# STM89C52.net
KiCad netlist of a schematic drawn in Altium Designer
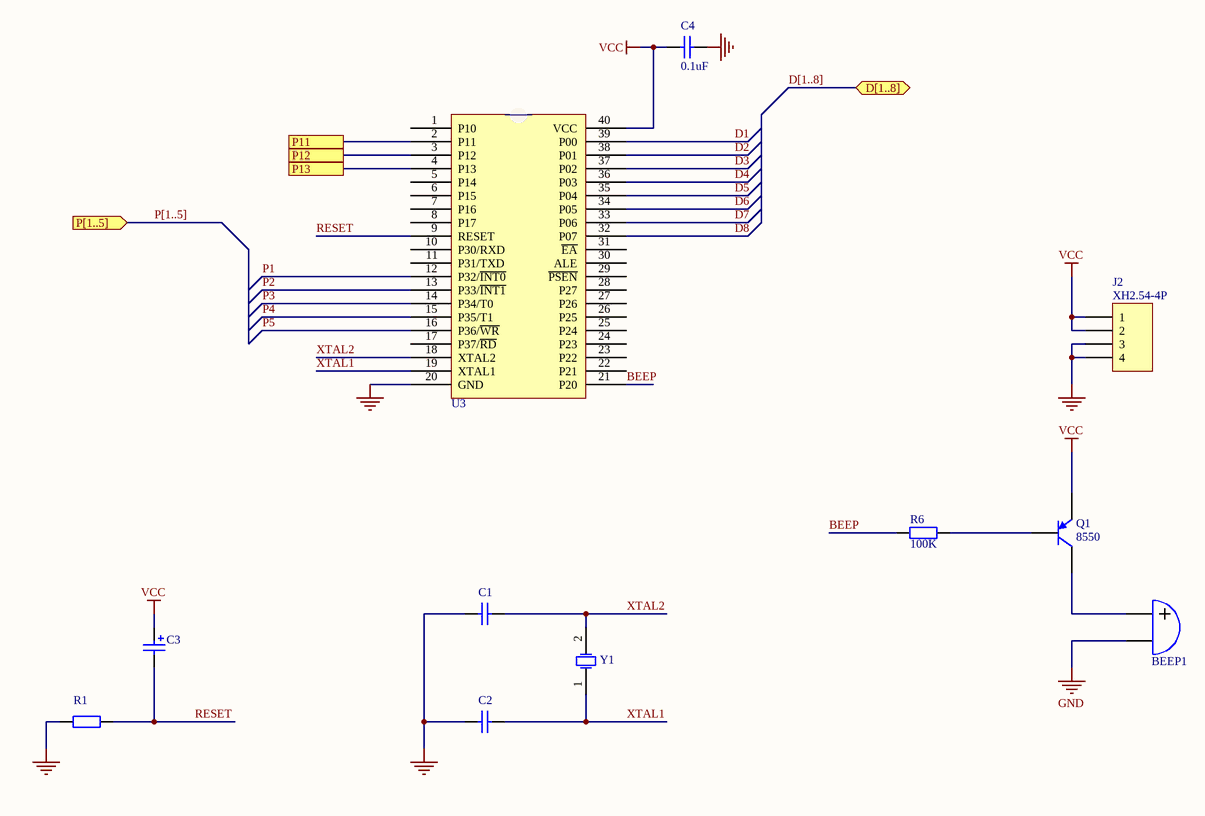
[diagram p0: STM89C52.SchDoc]

(export (version "E")
  (design (tool "Eeschema 10.0.6"))
  (components
    (comp (ref "BEEP1") (value "BEEP") (footprint "BEEP") (libsource (lib "TEST2024") (part "BEEP")))
    (comp (ref "C1")
      (value "Cap")
      (footprint "RAD-0.2")
      (description "Capacitor")
      (fields (field (name "PUBLISHER") "Altium Limited"))
      (libsource (lib "TEST2024") (part "Cap"))
    )
    (comp (ref "C2")
      (value "Cap")
      (footprint "RAD-0.2")
      (description "Capacitor")
      (fields (field (name "PUBLISHER") "Altium Limited"))
      (libsource (lib "TEST2024") (part "Cap"))
    )
    (comp (ref "C3")
      (value "Cap Pol1")
      (footprint "RB7.6-15")
      (description "Polarized Capacitor (Radial)")
      (fields (field (name "PUBLISHER") "Altium Limited"))
      (libsource (lib "TEST2024") (part "Cap Pol1"))
    )
    (comp (ref "C4")
      (value "0.1uF")
      (footprint "RAD-0.2")
      (description "Capacitor")
      (fields (field (name "Comment") "Cap") (field (name "PUBLISHER") "Altium Limited"))
      (libsource (lib "TEST2024") (part "Cap"))
    )
    (comp (ref "J2")
      (value "XH2.54-4P")
      (footprint "HDR1X4")
      (description "Header, 4-Pin")
      (fields (field (name "PUBLISHER") "Altium Limited"))
      (libsource (lib "TEST2024") (part "Header 4"))
    )
    (comp (ref "Q1") (value "8550") (footprint "PNP") (libsource (lib "TEST2024") (part "PNP")))
    (comp (ref "R1")
      (value "10K")
      (footprint "AXIAL-0.4")
      (description "Resistor")
      (fields (field (name "PUBLISHER") "Altium Limited"))
      (libsource (lib "TEST2024") (part "Res2"))
    )
    (comp (ref "R6") (value "100K") (footprint "RES") (libsource (lib "TEST2024") (part "Res")))
    (comp (ref "U3") (value "STC89C52") (footprint "DIP40") (libsource (lib "TEST2024") (part "STC89C52")))
    (comp (ref "Y1")
      (value "12MHZ")
      (footprint "XT12M")
      (description "Crystal Oscillator")
      (fields (field (name "PUBLISHER") "Altium Limited"))
      (libsource (lib "TEST2024") (part "XTAL"))
    )
  )
  (nets
    (net (code "1") (name "/BEEP") (class "Default")
      (node (ref "R6") (pin "1") (pinfunction "1_1") (pintype "passive"))
      (node (ref "U3") (pin "21") (pinfunction "P20_21") (pintype "passive"))
    )
    (net (code "2") (name "/D1") (class "Default")
      (node (ref "U3") (pin "39") (pinfunction "P00_39") (pintype "passive"))
    )
    (net (code "3") (name "/D2") (class "Default")
      (node (ref "U3") (pin "38") (pinfunction "P01_38") (pintype "passive"))
    )
    (net (code "4") (name "/D3") (class "Default")
      (node (ref "U3") (pin "37") (pinfunction "P02_37") (pintype "passive"))
    )
    (net (code "5") (name "/D4") (class "Default")
      (node (ref "U3") (pin "36") (pinfunction "P03_36") (pintype "passive"))
    )
    (net (code "6") (name "/D5") (class "Default")
      (node (ref "U3") (pin "35") (pinfunction "P04_35") (pintype "passive"))
    )
    (net (code "7") (name "/D6") (class "Default")
      (node (ref "U3") (pin "34") (pinfunction "P05_34") (pintype "passive"))
    )
    (net (code "8") (name "/D7") (class "Default")
      (node (ref "U3") (pin "33") (pinfunction "P06_33") (pintype "passive"))
    )
    (net (code "9") (name "/D8") (class "Default")
      (node (ref "U3") (pin "32") (pinfunction "P07_32") (pintype "passive"))
    )
    (net (code "11") (name "/P1") (class "Default")
      (node (ref "U3") (pin "12") (pinfunction "P32/~{INT0}_12") (pintype "passive"))
    )
    (net (code "12") (name "/P2") (class "Default")
      (node (ref "U3") (pin "13") (pinfunction "P33/~{INT1}_13") (pintype "passive"))
    )
    (net (code "13") (name "/P3") (class "Default")
      (node (ref "U3") (pin "14") (pinfunction "P34/T0_14") (pintype "passive"))
    )
    (net (code "14") (name "/P4") (class "Default")
      (node (ref "U3") (pin "15") (pinfunction "P35/T1_15") (pintype "passive"))
    )
    (net (code "15") (name "/P5") (class "Default")
      (node (ref "U3") (pin "16") (pinfunction "P36/~{WR}_16") (pintype "passive"))
    )
    (net (code "16") (name "/P11") (class "Default")
      (node (ref "U3") (pin "2") (pinfunction "P11_2") (pintype "passive"))
    )
    (net (code "17") (name "/P12") (class "Default")
      (node (ref "U3") (pin "3") (pinfunction "P12_3") (pintype "passive"))
    )
    (net (code "18") (name "/P13") (class "Default")
      (node (ref "U3") (pin "4") (pinfunction "P13_4") (pintype "passive"))
    )
    (net (code "20") (name "/RESET") (class "Default")
      (node (ref "C3") (pin "2") (pinfunction "2_2") (pintype "passive"))
      (node (ref "R1") (pin "2") (pinfunction "2_2") (pintype "passive"))
      (node (ref "U3") (pin "9") (pinfunction "RESET_9") (pintype "passive"))
    )
    (net (code "21") (name "/XTAL1") (class "Default")
      (node (ref "C2") (pin "1") (pinfunction "1_1") (pintype "passive"))
      (node (ref "U3") (pin "19") (pinfunction "XTAL1_19") (pintype "passive"))
      (node (ref "Y1") (pin "1") (pinfunction "OSC1_1") (pintype "passive"))
    )
    (net (code "22") (name "/XTAL2") (class "Default")
      (node (ref "C1") (pin "1") (pinfunction "1_1") (pintype "passive"))
      (node (ref "U3") (pin "18") (pinfunction "XTAL2_18") (pintype "passive"))
      (node (ref "Y1") (pin "2") (pinfunction "OSC2_2") (pintype "passive"))
    )
    (net (code "23") (name "GND") (class "Default")
      (node (ref "BEEP1") (pin "2") (pinfunction "2_2") (pintype "passive"))
      (node (ref "C1") (pin "2") (pinfunction "2_2") (pintype "passive"))
      (node (ref "C2") (pin "2") (pinfunction "2_2") (pintype "passive"))
      (node (ref "C4") (pin "1") (pinfunction "1_1") (pintype "passive"))
      (node (ref "J2") (pin "3") (pinfunction "3_3") (pintype "passive"))
      (node (ref "J2") (pin "4") (pinfunction "4_4") (pintype "passive"))
      (node (ref "R1") (pin "1") (pinfunction "1_1") (pintype "passive"))
      (node (ref "U3") (pin "20") (pinfunction "GND_20") (pintype "passive"))
    )
    (net (code "24") (name "Net-(Q1-B)") (class "Default")
      (node (ref "Q1") (pin "2") (pinfunction "B_2") (pintype "passive"))
      (node (ref "R6") (pin "2") (pinfunction "2_2") (pintype "passive"))
    )
    (net (code "25") (name "Net-(Q1-C)") (class "Default")
      (node (ref "BEEP1") (pin "1") (pinfunction "1_1") (pintype "passive"))
      (node (ref "Q1") (pin "3") (pinfunction "C_3") (pintype "passive"))
    )
    (net (code "26") (name "VCC") (class "Default")
      (node (ref "C3") (pin "1") (pinfunction "1_1") (pintype "passive"))
      (node (ref "C4") (pin "2") (pinfunction "2_2") (pintype "passive"))
      (node (ref "J2") (pin "1") (pinfunction "1_1") (pintype "passive"))
      (node (ref "J2") (pin "2") (pinfunction "2_2") (pintype "passive"))
      (node (ref "Q1") (pin "1") (pinfunction "E_1") (pintype "passive"))
      (node (ref "U3") (pin "40") (pinfunction "VCC_40") (pintype "passive"))
    )
    (net (code "27") (name "unconnected-(U3-ALE-Pad30)") (class "Default")
      (node (ref "U3") (pin "30") (pinfunction "ALE_30") (pintype "passive"))
    )
    (net (code "28") (name "unconnected-(U3-P10-Pad1)") (class "Default")
      (node (ref "U3") (pin "1") (pinfunction "P10_1") (pintype "passive"))
    )
    (net (code "29") (name "unconnected-(U3-P14-Pad5)") (class "Default")
      (node (ref "U3") (pin "5") (pinfunction "P14_5") (pintype "passive"))
    )
    (net (code "30") (name "unconnected-(U3-P15-Pad6)") (class "Default")
      (node (ref "U3") (pin "6") (pinfunction "P15_6") (pintype "passive"))
    )
    (net (code "31") (name "unconnected-(U3-P16-Pad7)") (class "Default")
      (node (ref "U3") (pin "7") (pinfunction "P16_7") (pintype "passive"))
    )
    (net (code "32") (name "unconnected-(U3-P17-Pad8)") (class "Default")
      (node (ref "U3") (pin "8") (pinfunction "P17_8") (pintype "passive"))
    )
    (net (code "33") (name "unconnected-(U3-P21-Pad22)") (class "Default")
      (node (ref "U3") (pin "22") (pinfunction "P21_22") (pintype "passive"))
    )
    (net (code "34") (name "unconnected-(U3-P22-Pad23)") (class "Default")
      (node (ref "U3") (pin "23") (pinfunction "P22_23") (pintype "passive"))
    )
    (net (code "35") (name "unconnected-(U3-P23-Pad24)") (class "Default")
      (node (ref "U3") (pin "24") (pinfunction "P23_24") (pintype "passive"))
    )
    (net (code "36") (name "unconnected-(U3-P24-Pad25)") (class "Default")
      (node (ref "U3") (pin "25") (pinfunction "P24_25") (pintype "passive"))
    )
    (net (code "37") (name "unconnected-(U3-P25-Pad26)") (class "Default")
      (node (ref "U3") (pin "26") (pinfunction "P25_26") (pintype "passive"))
    )
    (net (code "38") (name "unconnected-(U3-P26-Pad27)") (class "Default")
      (node (ref "U3") (pin "27") (pinfunction "P26_27") (pintype "passive"))
    )
    (net (code "39") (name "unconnected-(U3-P27-Pad28)") (class "Default")
      (node (ref "U3") (pin "28") (pinfunction "P27_28") (pintype "passive"))
    )
    (net (code "40") (name "unconnected-(U3-P30{slash}RXD-Pad10)") (class "Default")
      (node (ref "U3") (pin "10") (pinfunction "P30/RXD_10") (pintype "passive"))
    )
    (net (code "41") (name "unconnected-(U3-P31{slash}TXD-Pad11)") (class "Default")
      (node (ref "U3") (pin "11") (pinfunction "P31/TXD_11") (pintype "passive"))
    )
    (net (code "42") (name "unconnected-(U3-P37{slash}~{RD}-Pad17)") (class "Default")
      (node (ref "U3") (pin "17") (pinfunction "P37/~{RD}_17") (pintype "passive"))
    )
    (net (code "43") (name "unconnected-(U3-~{EA}-Pad31)") (class "Default")
      (node (ref "U3") (pin "31") (pinfunction "~{EA}_31") (pintype "passive"))
    )
    (net (code "44") (name "unconnected-(U3-~{PSEN}-Pad29)") (class "Default")
      (node (ref "U3") (pin "29") (pinfunction "~{PSEN}_29") (pintype "passive"))
    )
  )
)
